# 9_STM32F407_Controller.net
KiCad netlist of a schematic drawn in Altium Designer
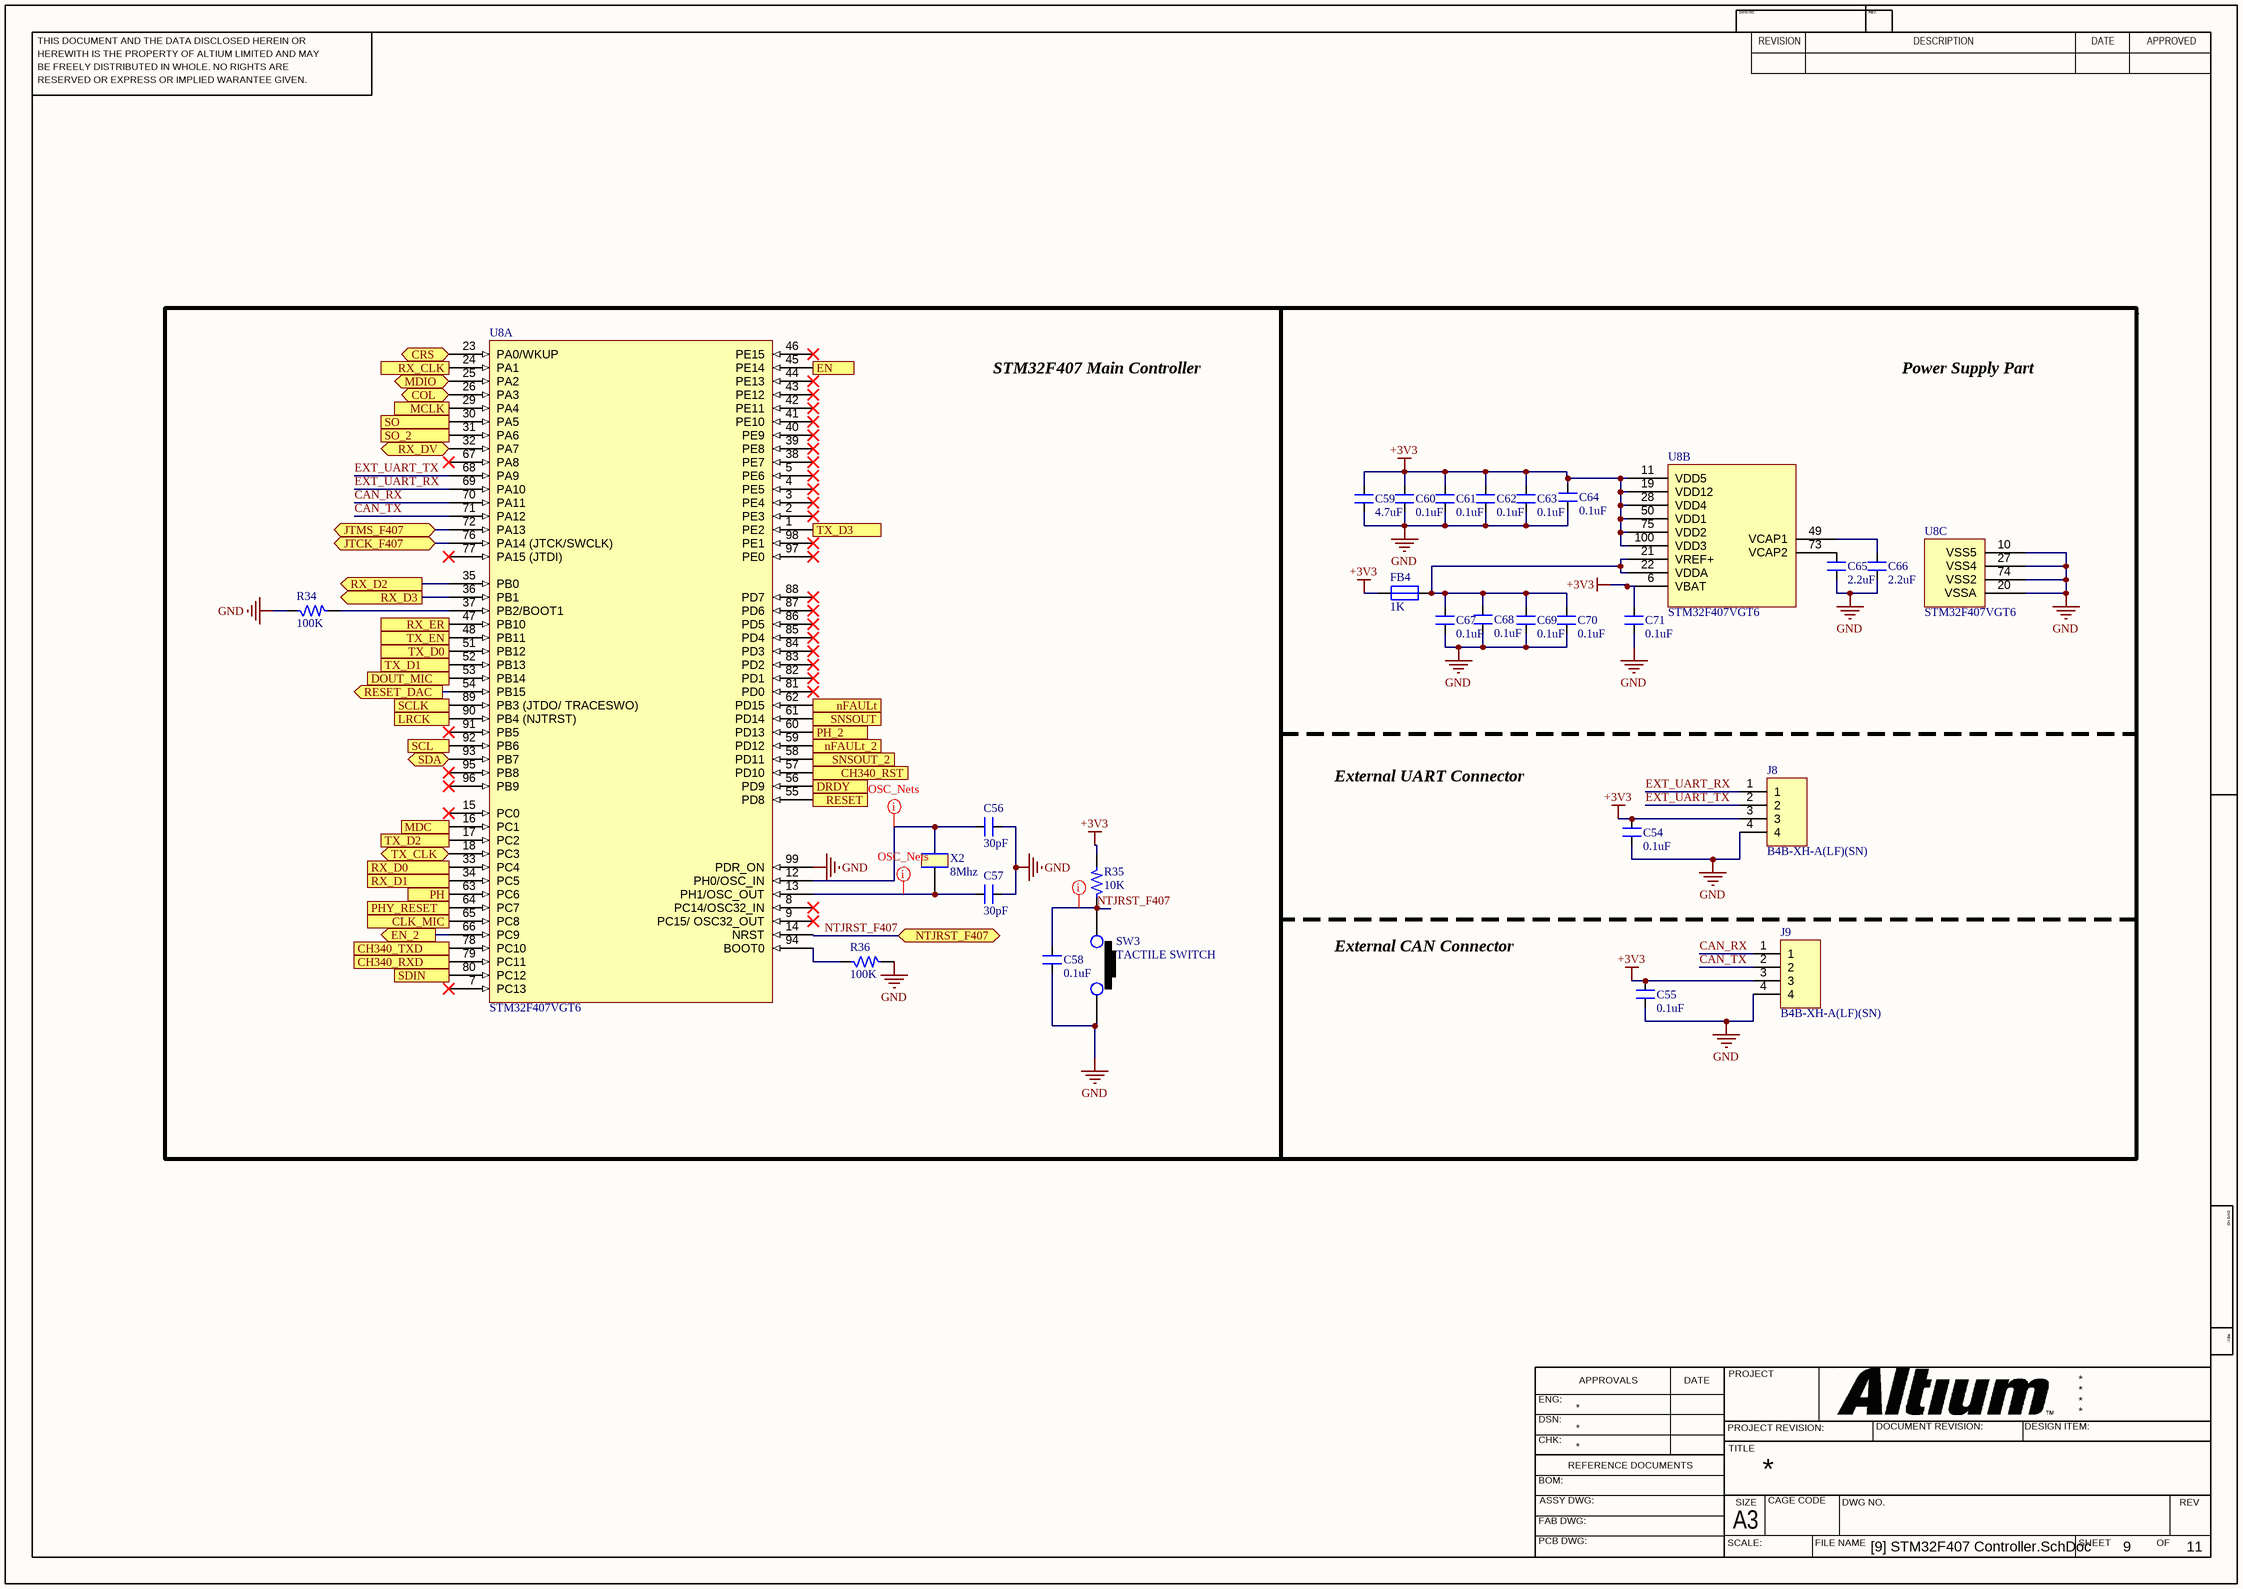
[diagram p0: [9] STM32F407 Controller.SchDoc]

(export (version "E")
  (design (tool "Eeschema 10.0.6"))
  (components
    (comp (ref "C54")
      (value "0.1uF")
      (footprint "CAP_0805")
      (description "0.1µF ±10% 50V Ceramic Capacitor X7R 0805 (2012 Metric)")
      (fields
        (field (name "MANUFACTURER") "Samsung")
        (field (name "MANUFACTURER PART NUMBER") "CL21B104KBCNNNC")
      )
      (libsource (lib "ESTEEMPCBLIB") (part "CAP_0.1uF-50V-10%-0805"))
    )
    (comp (ref "C55")
      (value "0.1uF")
      (footprint "CAP_0805")
      (description "0.1µF ±10% 50V Ceramic Capacitor X7R 0805 (2012 Metric)")
      (fields
        (field (name "MANUFACTURER") "Samsung")
        (field (name "MANUFACTURER PART NUMBER") "CL21B104KBCNNNC")
      )
      (libsource (lib "ESTEEMPCBLIB") (part "CAP_0.1uF-50V-10%-0805"))
    )
    (comp (ref "C56")
      (value "30pF")
      (footprint "CAP_0805")
      (description "±10% 50V Ceramic Capacitor C0G, NP0 0805 (2012 Metric)")
      (fields
        (field (name "MANUFACTURER PART NUMBER") "C0805C300K5GAC7800")
        (field (name "MANUFACTURER") "KEMET")
      )
      (libsource (lib "ESTEEMPCBLIB") (part "CAP_30pF-50V-10%-0805"))
    )
    (comp (ref "C57")
      (value "30pF")
      (footprint "CAP_0805")
      (description "±10% 50V Ceramic Capacitor C0G, NP0 0805 (2012 Metric)")
      (fields
        (field (name "MANUFACTURER PART NUMBER") "C0805C300K5GAC7800")
        (field (name "MANUFACTURER") "KEMET")
      )
      (libsource (lib "ESTEEMPCBLIB") (part "CAP_30pF-50V-10%-0805"))
    )
    (comp (ref "C58")
      (value "0.1uF")
      (footprint "CAP_0805")
      (description "0.1µF ±10% 50V Ceramic Capacitor X7R 0805 (2012 Metric)")
      (fields
        (field (name "MANUFACTURER") "Samsung")
        (field (name "MANUFACTURER PART NUMBER") "CL21B104KBCNNNC")
      )
      (libsource (lib "ESTEEMPCBLIB") (part "CAP_0.1uF-50V-10%-0805"))
    )
    (comp (ref "C59")
      (value "4.7uF")
      (footprint "CAP_0805")
      (description "4.7µF ±10% 50V Ceramic Capacitor X5R 0805 (2012 Metric)")
      (fields
        (field (name "MANUFACTURER") "Yageo")
        (field (name "MANUFACTURER PART NUMBER") "GRM21BR61H475KE51L")
      )
      (libsource (lib "ESTEEMPCBLIB") (part "CAP_4.7uF-50V-10%-0805"))
    )
    (comp (ref "C60")
      (value "0.1uF")
      (footprint "CAP_0805")
      (description "0.1µF ±10% 50V Ceramic Capacitor X7R 0805 (2012 Metric)")
      (fields
        (field (name "MANUFACTURER") "Samsung")
        (field (name "MANUFACTURER PART NUMBER") "CL21B104KBCNNNC")
      )
      (libsource (lib "ESTEEMPCBLIB") (part "CAP_0.1uF-50V-10%-0805"))
    )
    (comp (ref "C61")
      (value "0.1uF")
      (footprint "CAP_0805")
      (description "0.1µF ±10% 50V Ceramic Capacitor X7R 0805 (2012 Metric)")
      (fields
        (field (name "MANUFACTURER") "Samsung")
        (field (name "MANUFACTURER PART NUMBER") "CL21B104KBCNNNC")
      )
      (libsource (lib "ESTEEMPCBLIB") (part "CAP_0.1uF-50V-10%-0805"))
    )
    (comp (ref "C62")
      (value "0.1uF")
      (footprint "CAP_0805")
      (description "0.1µF ±10% 50V Ceramic Capacitor X7R 0805 (2012 Metric)")
      (fields
        (field (name "MANUFACTURER") "Samsung")
        (field (name "MANUFACTURER PART NUMBER") "CL21B104KBCNNNC")
      )
      (libsource (lib "ESTEEMPCBLIB") (part "CAP_0.1uF-50V-10%-0805"))
    )
    (comp (ref "C63")
      (value "0.1uF")
      (footprint "CAP_0805")
      (description "0.1µF ±10% 50V Ceramic Capacitor X7R 0805 (2012 Metric)")
      (fields
        (field (name "MANUFACTURER") "Samsung")
        (field (name "MANUFACTURER PART NUMBER") "CL21B104KBCNNNC")
      )
      (libsource (lib "ESTEEMPCBLIB") (part "CAP_0.1uF-50V-10%-0805"))
    )
    (comp (ref "C64")
      (value "0.1uF")
      (footprint "CAP_0805")
      (description "0.1µF ±10% 50V Ceramic Capacitor X7R 0805 (2012 Metric)")
      (fields
        (field (name "MANUFACTURER") "Samsung")
        (field (name "MANUFACTURER PART NUMBER") "CL21B104KBCNNNC")
      )
      (libsource (lib "ESTEEMPCBLIB") (part "CAP_0.1uF-50V-10%-0805"))
    )
    (comp (ref "C65")
      (value "2.2uF")
      (footprint "CAP_0805")
      (description "2.2µF ±10% 25V Ceramic Capacitor X7R 0805 (2012 Metric)")
      (fields
        (field (name "MANUFACTURER") "KEMET")
        (field (name "MANUFACTURER PART NUMBER") "CL21B225KAFNFNE")
      )
      (libsource (lib "ESTEEMPCBLIB") (part "CAP_2.2uF-25V-10%-0805"))
    )
    (comp (ref "C66")
      (value "2.2uF")
      (footprint "CAP_0805")
      (description "2.2µF ±10% 25V Ceramic Capacitor X7R 0805 (2012 Metric)")
      (fields
        (field (name "MANUFACTURER") "KEMET")
        (field (name "MANUFACTURER PART NUMBER") "CL21B225KAFNFNE")
      )
      (libsource (lib "ESTEEMPCBLIB") (part "CAP_2.2uF-25V-10%-0805"))
    )
    (comp (ref "C67")
      (value "0.1uF")
      (footprint "CAP_0805")
      (description "0.1µF ±10% 50V Ceramic Capacitor X7R 0805 (2012 Metric)")
      (fields
        (field (name "MANUFACTURER") "Samsung")
        (field (name "MANUFACTURER PART NUMBER") "CL21B104KBCNNNC")
      )
      (libsource (lib "ESTEEMPCBLIB") (part "CAP_0.1uF-50V-10%-0805"))
    )
    (comp (ref "C68")
      (value "0.1uF")
      (footprint "CAP_0805")
      (description "0.1µF ±10% 50V Ceramic Capacitor X7R 0805 (2012 Metric)")
      (fields
        (field (name "MANUFACTURER") "Samsung")
        (field (name "MANUFACTURER PART NUMBER") "CL21B104KBCNNNC")
      )
      (libsource (lib "ESTEEMPCBLIB") (part "CAP_0.1uF-50V-10%-0805"))
    )
    (comp (ref "C69")
      (value "0.1uF")
      (footprint "CAP_0805")
      (description "0.1µF ±10% 50V Ceramic Capacitor X7R 0805 (2012 Metric)")
      (fields
        (field (name "MANUFACTURER") "Samsung")
        (field (name "MANUFACTURER PART NUMBER") "CL21B104KBCNNNC")
      )
      (libsource (lib "ESTEEMPCBLIB") (part "CAP_0.1uF-50V-10%-0805"))
    )
    (comp (ref "C70")
      (value "0.1uF")
      (footprint "CAP_0805")
      (description "0.1µF ±10% 50V Ceramic Capacitor X7R 0805 (2012 Metric)")
      (fields
        (field (name "MANUFACTURER") "Samsung")
        (field (name "MANUFACTURER PART NUMBER") "CL21B104KBCNNNC")
      )
      (libsource (lib "ESTEEMPCBLIB") (part "CAP_0.1uF-50V-10%-0805"))
    )
    (comp (ref "C71")
      (value "0.1uF")
      (footprint "CAP_0805")
      (description "0.1µF ±10% 50V Ceramic Capacitor X7R 0805 (2012 Metric)")
      (fields
        (field (name "MANUFACTURER") "Samsung")
        (field (name "MANUFACTURER PART NUMBER") "CL21B104KBCNNNC")
      )
      (libsource (lib "ESTEEMPCBLIB") (part "CAP_0.1uF-50V-10%-0805"))
    )
    (comp (ref "FB4")
      (value "1K")
      (footprint "IND_0805")
      (description "1 kOhms @ 100MHz 1 Power Line Ferrite Bead 0805 (2012 Metric) 1.6A")
      (fields
        (field (name "MANUFACTURER") "Laird")
        (field (name "MANUFACTURER PART NUMBER") "BLM21SP102SH1D")
      )
      (libsource (lib "ESTEEMPCBLIB") (part "FB_1K-100MHZ-1.6A-0805"))
    )
    (comp (ref "J8")
      (value "B4B-XH-A(LF)(SN)")
      (footprint "CON4_100_B4B-XH-A_TH_ST")
      (description "4 Pins, 1 Row 2.54mm Pitch, straight Connector, male")
      (fields (field (name "MANUFACTURER") "Wurth Electronics") (field (name "MATING PART NUMBER") "XHP-4"))
      (libsource (lib "ESTEEMPCBLIB") (part "CON-PLG_4X1-100-ST-TH"))
    )
    (comp (ref "J9")
      (value "B4B-XH-A(LF)(SN)")
      (footprint "CON4_100_B4B-XH-A_TH_ST")
      (description "4 Pins, 1 Row 2.54mm Pitch, straight Connector, male")
      (fields (field (name "MANUFACTURER") "Wurth Electronics") (field (name "MATING PART NUMBER") "XHP-4"))
      (libsource (lib "ESTEEMPCBLIB") (part "CON-PLG_4X1-100-ST-TH"))
    )
    (comp (ref "R34")
      (value "100K")
      (footprint "RES_0603")
      (description "100 kOhms ±1% 0.1W, 1/10W Chip Resistor 0603 (1608 Metric) Automotive AEC-Q200 Thick Film")
      (fields
        (field (name "MANUFACTURER") "Stackpole Electronics")
        (field (name "MANUFACTURER PART NUMBER") "RMCF0603FT100K")
      )
      (libsource (lib "ESTEEMPCBLIB") (part "RES_100K-0.1W-1%-0603"))
    )
    (comp (ref "R35")
      (value "10K")
      (footprint "RES_0603")
      (description "10 kOhms ±1% 0.1W, 1/10W Chip Resistor 0603 (1608 Metric) Automotive AEC-Q200 Thick Film")
      (fields (field (name "MANUFACTURER") "Walsin") (field (name "MANUFACTURER PART NUMBER") "WR06X1002FTL"))
      (libsource (lib "ESTEEMPCBLIB") (part "RES_10K-0.1W-1%-0603"))
    )
    (comp (ref "R36")
      (value "100K")
      (footprint "RES_0603")
      (description "100 kOhms ±1% 0.1W, 1/10W Chip Resistor 0603 (1608 Metric) Automotive AEC-Q200 Thick Film")
      (fields
        (field (name "MANUFACTURER") "Stackpole Electronics")
        (field (name "MANUFACTURER PART NUMBER") "RMCF0603FT100K")
      )
      (libsource (lib "ESTEEMPCBLIB") (part "RES_100K-0.1W-1%-0603"))
    )
    (comp (ref "SW3")
      (value "TACTILE SWITCH")
      (footprint "SW_342_SMD")
      (description "Tactile Switch SPST-NO Top Actuated Surface Mount")
      (fields
        (field (name "MANUFACTURER") "ITT C&K")
        (field (name "MANUFACTURER PART NUMBER") "RS-282G05A3-SMRT")
      )
      (libsource (lib "ESTEEMPCBLIB") (part "SW1_RS-282G05A3-SMRT-SMD"))
    )
    (comp (ref "U8")
      (value "STM32F407VGT6")
      (footprint "QFN100_19.6_669_58X10_SMD")
      (description "ARM® Cortex®-M4 STM32F4 Microcontroller IC 32-Bit 168MHz 1MB (1M x 8) FLASH 100-LQFP (14x14)")
      (fields (field (name "MANUFACTURER") "STMicroelectronics"))
      (libsource (lib "ESTEEMPCBLIB") (part "IC_STM32F407VGT6"))
    )
    (comp (ref "X2")
      (value "8Mhz")
      (footprint "XTAL_314_240X47_SMD")
      (description "8MHz ±30ppm Crystal 32pF 60 Ohms HC-49/US")
      (fields
        (field (name "MANUFACTURER") "Fox Electronics")
        (field (name "MANUFACTURER PART NUMBER") "ECS-80-32-5PX-TR")
      )
      (libsource (lib "ESTEEMPCBLIB") (part "XTAL_8MHZ-ECS-80-32-5PX-SMD"))
    )
  )
  (nets
    (net (code "1") (name "+3V3") (class "Default")
      (node (ref "C54") (pin "2") (pinfunction "2_2") (pintype "passive"))
      (node (ref "C55") (pin "2") (pinfunction "2_2") (pintype "passive"))
      (node (ref "C59") (pin "2") (pinfunction "2_2") (pintype "passive"))
      (node (ref "C60") (pin "2") (pinfunction "2_2") (pintype "passive"))
      (node (ref "C61") (pin "2") (pinfunction "2_2") (pintype "passive"))
      (node (ref "C62") (pin "2") (pinfunction "2_2") (pintype "passive"))
      (node (ref "C63") (pin "2") (pinfunction "2_2") (pintype "passive"))
      (node (ref "C64") (pin "2") (pinfunction "2_2") (pintype "passive"))
      (node (ref "C71") (pin "2") (pinfunction "2_2") (pintype "passive"))
      (node (ref "FB4") (pin "1") (pinfunction "1_1") (pintype "passive"))
      (node (ref "J8") (pin "3") (pinfunction "3_3") (pintype "passive"))
      (node (ref "J9") (pin "3") (pinfunction "3_3") (pintype "passive"))
      (node (ref "R35") (pin "2") (pinfunction "2_2") (pintype "passive"))
      (node (ref "U8") (pin "100") (pinfunction "VDD3_100") (pintype "passive"))
      (node (ref "U8") (pin "11") (pinfunction "VDD5_11") (pintype "passive"))
      (node (ref "U8") (pin "19") (pinfunction "VDD12_19") (pintype "passive"))
      (node (ref "U8") (pin "28") (pinfunction "VDD4_28") (pintype "passive"))
      (node (ref "U8") (pin "50") (pinfunction "VDD1_50") (pintype "passive"))
      (node (ref "U8") (pin "6") (pinfunction "VBAT_6") (pintype "passive"))
      (node (ref "U8") (pin "75") (pinfunction "VDD2_75") (pintype "passive"))
    )
    (net (code "2") (name "/CAN_RX") (class "Default")
      (node (ref "J9") (pin "1") (pinfunction "1_1") (pintype "passive"))
      (node (ref "U8") (pin "70") (pinfunction "PA11_70") (pintype "input"))
    )
    (net (code "3") (name "/CAN_TX") (class "Default")
      (node (ref "J9") (pin "2") (pinfunction "2_2") (pintype "passive"))
      (node (ref "U8") (pin "71") (pinfunction "PA12_71") (pintype "input"))
    )
    (net (code "4") (name "/CH340_RST") (class "Default")
      (node (ref "U8") (pin "57") (pinfunction "PD10_57") (pintype "input"))
    )
    (net (code "5") (name "/CH340_RXD") (class "Default")
      (node (ref "U8") (pin "79") (pinfunction "PC11_79") (pintype "input"))
    )
    (net (code "6") (name "/CH340_TXD") (class "Default")
      (node (ref "U8") (pin "78") (pinfunction "PC10_78") (pintype "input"))
    )
    (net (code "7") (name "/CLK_MIC") (class "Default")
      (node (ref "U8") (pin "65") (pinfunction "PC8_65") (pintype "input"))
    )
    (net (code "8") (name "/COL") (class "Default")
      (node (ref "U8") (pin "26") (pinfunction "PA3_26") (pintype "input"))
    )
    (net (code "9") (name "/CRS") (class "Default")
      (node (ref "U8") (pin "23") (pinfunction "PA0/WKUP_23") (pintype "input"))
    )
    (net (code "10") (name "/DOUT_MIC") (class "Default")
      (node (ref "U8") (pin "53") (pinfunction "PB14_53") (pintype "input"))
    )
    (net (code "11") (name "/DRDY") (class "Default")
      (node (ref "U8") (pin "56") (pinfunction "PD9_56") (pintype "input"))
    )
    (net (code "12") (name "/EN") (class "Default")
      (node (ref "U8") (pin "45") (pinfunction "PE14_45") (pintype "input"))
    )
    (net (code "13") (name "/EN_2") (class "Default")
      (node (ref "U8") (pin "66") (pinfunction "PC9_66") (pintype "input"))
    )
    (net (code "14") (name "/EXT_UART_RX") (class "Default")
      (node (ref "J8") (pin "1") (pinfunction "1_1") (pintype "passive"))
      (node (ref "U8") (pin "69") (pinfunction "PA10_69") (pintype "input"))
    )
    (net (code "15") (name "/EXT_UART_TX") (class "Default")
      (node (ref "J8") (pin "2") (pinfunction "2_2") (pintype "passive"))
      (node (ref "U8") (pin "68") (pinfunction "PA9_68") (pintype "input"))
    )
    (net (code "16") (name "/JTCK_F407") (class "Default")
      (node (ref "U8") (pin "76") (pinfunction "PA14_(JTCK/SWCLK)_76") (pintype "input"))
    )
    (net (code "17") (name "/JTMS_F407") (class "Default")
      (node (ref "U8") (pin "72") (pinfunction "PA13_72") (pintype "input"))
    )
    (net (code "18") (name "/LRCK") (class "Default")
      (node (ref "U8") (pin "90") (pinfunction "PB4_(NJTRST)_90") (pintype "input"))
    )
    (net (code "19") (name "/MCLK") (class "Default")
      (node (ref "U8") (pin "29") (pinfunction "PA4_29") (pintype "input"))
    )
    (net (code "20") (name "/MDC") (class "Default")
      (node (ref "U8") (pin "16") (pinfunction "PC1_16") (pintype "input"))
    )
    (net (code "21") (name "/MDIO") (class "Default")
      (node (ref "U8") (pin "25") (pinfunction "PA2_25") (pintype "input"))
    )
    (net (code "22") (name "/NTJRST_F407") (class "Default")
      (node (ref "C58") (pin "2") (pinfunction "2_2") (pintype "passive"))
      (node (ref "R35") (pin "1") (pinfunction "1_1") (pintype "passive"))
      (node (ref "SW3") (pin "1") (pinfunction "1_1") (pintype "passive"))
      (node (ref "U8") (pin "14") (pinfunction "NRST_14") (pintype "input"))
    )
    (net (code "23") (name "/PH") (class "Default")
      (node (ref "U8") (pin "63") (pinfunction "PC6_63") (pintype "input"))
    )
    (net (code "24") (name "/PHY_RESET") (class "Default")
      (node (ref "U8") (pin "64") (pinfunction "PC7_64") (pintype "input"))
    )
    (net (code "25") (name "/PH_2") (class "Default")
      (node (ref "U8") (pin "60") (pinfunction "PD13_60") (pintype "input"))
    )
    (net (code "26") (name "/RESET") (class "Default")
      (node (ref "U8") (pin "55") (pinfunction "PD8_55") (pintype "input"))
    )
    (net (code "27") (name "/RESET_DAC") (class "Default")
      (node (ref "U8") (pin "54") (pinfunction "PB15_54") (pintype "input"))
    )
    (net (code "28") (name "/RX_CLK") (class "Default")
      (node (ref "U8") (pin "24") (pinfunction "PA1_24") (pintype "input"))
    )
    (net (code "29") (name "/RX_D0") (class "Default")
      (node (ref "U8") (pin "33") (pinfunction "PC4_33") (pintype "input"))
    )
    (net (code "30") (name "/RX_D1") (class "Default")
      (node (ref "U8") (pin "34") (pinfunction "PC5_34") (pintype "input"))
    )
    (net (code "31") (name "/RX_D2") (class "Default")
      (node (ref "U8") (pin "35") (pinfunction "PB0_35") (pintype "input"))
    )
    (net (code "32") (name "/RX_D3") (class "Default")
      (node (ref "U8") (pin "36") (pinfunction "PB1_36") (pintype "input"))
    )
    (net (code "33") (name "/RX_DV") (class "Default")
      (node (ref "U8") (pin "32") (pinfunction "PA7_32") (pintype "input"))
    )
    (net (code "34") (name "/RX_ER") (class "Default")
      (node (ref "U8") (pin "47") (pinfunction "PB10_47") (pintype "input"))
    )
    (net (code "35") (name "/SCL") (class "Default")
      (node (ref "U8") (pin "92") (pinfunction "PB6_92") (pintype "input"))
    )
    (net (code "36") (name "/SCLK") (class "Default")
      (node (ref "U8") (pin "89") (pinfunction "PB3_(JTDO/_TRACESWO)_89") (pintype "input"))
    )
    (net (code "37") (name "/SDA") (class "Default")
      (node (ref "U8") (pin "93") (pinfunction "PB7_93") (pintype "input"))
    )
    (net (code "38") (name "/SDIN") (class "Default")
      (node (ref "U8") (pin "80") (pinfunction "PC12_80") (pintype "input"))
    )
    (net (code "39") (name "/SNSOUT") (class "Default")
      (node (ref "U8") (pin "61") (pinfunction "PD14_61") (pintype "input"))
    )
    (net (code "40") (name "/SNSOUT_2") (class "Default")
      (node (ref "U8") (pin "58") (pinfunction "PD11_58") (pintype "input"))
    )
    (net (code "41") (name "/SO") (class "Default")
      (node (ref "U8") (pin "30") (pinfunction "PA5_30") (pintype "input"))
    )
    (net (code "42") (name "/SO_2") (class "Default")
      (node (ref "U8") (pin "31") (pinfunction "PA6_31") (pintype "input"))
    )
    (net (code "43") (name "/TX_CLK") (class "Default")
      (node (ref "U8") (pin "18") (pinfunction "PC3_18") (pintype "input"))
    )
    (net (code "44") (name "/TX_D0") (class "Default")
      (node (ref "U8") (pin "51") (pinfunction "PB12_51") (pintype "input"))
    )
    (net (code "45") (name "/TX_D1") (class "Default")
      (node (ref "U8") (pin "52") (pinfunction "PB13_52") (pintype "input"))
    )
    (net (code "46") (name "/TX_D2") (class "Default")
      (node (ref "U8") (pin "17") (pinfunction "PC2_17") (pintype "input"))
    )
    (net (code "47") (name "/TX_D3") (class "Default")
      (node (ref "U8") (pin "1") (pinfunction "PE2_1") (pintype "input"))
    )
    (net (code "48") (name "/TX_EN") (class "Default")
      (node (ref "U8") (pin "48") (pinfunction "PB11_48") (pintype "input"))
    )
    (net (code "49") (name "/nFAULt") (class "Default")
      (node (ref "U8") (pin "62") (pinfunction "PD15_62") (pintype "input"))
    )
    (net (code "50") (name "/nFAULt_2") (class "Default")
      (node (ref "U8") (pin "59") (pinfunction "PD12_59") (pintype "input"))
    )
    (net (code "51") (name "GND") (class "Default")
      (node (ref "C54") (pin "1") (pinfunction "1_1") (pintype "passive"))
      (node (ref "C55") (pin "1") (pinfunction "1_1") (pintype "passive"))
      (node (ref "C56") (pin "1") (pinfunction "1_1") (pintype "passive"))
      (node (ref "C57") (pin "1") (pinfunction "1_1") (pintype "passive"))
      (node (ref "C58") (pin "1") (pinfunction "1_1") (pintype "passive"))
      (node (ref "C59") (pin "1") (pinfunction "1_1") (pintype "passive"))
      (node (ref "C60") (pin "1") (pinfunction "1_1") (pintype "passive"))
      (node (ref "C61") (pin "1") (pinfunction "1_1") (pintype "passive"))
      (node (ref "C62") (pin "1") (pinfunction "1_1") (pintype "passive"))
      (node (ref "C63") (pin "1") (pinfunction "1_1") (pintype "passive"))
      (node (ref "C64") (pin "1") (pinfunction "1_1") (pintype "passive"))
      (node (ref "C65") (pin "1") (pinfunction "1_1") (pintype "passive"))
      (node (ref "C66") (pin "1") (pinfunction "1_1") (pintype "passive"))
      (node (ref "C67") (pin "1") (pinfunction "1_1") (pintype "passive"))
      (node (ref "C68") (pin "1") (pinfunction "1_1") (pintype "passive"))
      (node (ref "C69") (pin "1") (pinfunction "1_1") (pintype "passive"))
      (node (ref "C70") (pin "1") (pinfunction "1_1") (pintype "passive"))
      (node (ref "C71") (pin "1") (pinfunction "1_1") (pintype "passive"))
      (node (ref "J8") (pin "4") (pinfunction "4_4") (pintype "passive"))
      (node (ref "J9") (pin "4") (pinfunction "4_4") (pintype "passive"))
      (node (ref "R34") (pin "1") (pinfunction "1_1") (pintype "passive"))
      (node (ref "R36") (pin "2") (pinfunction "2_2") (pintype "passive"))
      (node (ref "SW3") (pin "2") (pinfunction "2_2") (pintype "passive"))
      (node (ref "U8") (pin "10") (pinfunction "VSS5_10") (pintype "passive"))
      (node (ref "U8") (pin "20") (pinfunction "VSSA_20") (pintype "passive"))
      (node (ref "U8") (pin "27") (pinfunction "VSS4_27") (pintype "passive"))
      (node (ref "U8") (pin "74") (pinfunction "VSS2_74") (pintype "passive"))
      (node (ref "U8") (pin "99") (pinfunction "PDR_ON_99") (pintype "input"))
    )
    (net (code "52") (name "Net-(U8A-BOOT0)") (class "Default")
      (node (ref "R36") (pin "1") (pinfunction "1_1") (pintype "passive"))
      (node (ref "U8") (pin "94") (pinfunction "BOOT0_94") (pintype "input"))
    )
    (net (code "53") (name "Net-(U8A-PB2{slash}BOOT1)") (class "Default")
      (node (ref "R34") (pin "2") (pinfunction "2_2") (pintype "passive"))
      (node (ref "U8") (pin "37") (pinfunction "PB2/BOOT1_37") (pintype "input"))
    )
    (net (code "54") (name "Net-(U8A-PH0{slash}OSC_IN)") (class "Default")
      (node (ref "C56") (pin "2") (pinfunction "2_2") (pintype "passive"))
      (node (ref "U8") (pin "12") (pinfunction "PH0/OSC_IN_12") (pintype "input"))
      (node (ref "X2") (pin "2") (pinfunction "2_2") (pintype "passive"))
    )
    (net (code "55") (name "Net-(U8A-PH1{slash}OSC_OUT)") (class "Default")
      (node (ref "C57") (pin "2") (pinfunction "2_2") (pintype "passive"))
      (node (ref "U8") (pin "13") (pinfunction "PH1/OSC_OUT_13") (pintype "input"))
      (node (ref "X2") (pin "1") (pinfunction "1_1") (pintype "passive"))
    )
    (net (code "56") (name "Net-(U8B-VCAP1)") (class "Default")
      (node (ref "C66") (pin "2") (pinfunction "2_2") (pintype "passive"))
      (node (ref "U8") (pin "49") (pinfunction "VCAP1_49") (pintype "passive"))
    )
    (net (code "57") (name "Net-(U8B-VCAP2)") (class "Default")
      (node (ref "C65") (pin "2") (pinfunction "2_2") (pintype "passive"))
      (node (ref "U8") (pin "73") (pinfunction "VCAP2_73") (pintype "passive"))
    )
    (net (code "58") (name "Net-(U8B-VDDA)") (class "Default")
      (node (ref "C67") (pin "2") (pinfunction "2_2") (pintype "passive"))
      (node (ref "C68") (pin "2") (pinfunction "2_2") (pintype "passive"))
      (node (ref "C69") (pin "2") (pinfunction "2_2") (pintype "passive"))
      (node (ref "C70") (pin "2") (pinfunction "2_2") (pintype "passive"))
      (node (ref "FB4") (pin "2") (pinfunction "2_2") (pintype "passive"))
      (node (ref "U8") (pin "21") (pinfunction "VREF+_21") (pintype "passive"))
      (node (ref "U8") (pin "22") (pinfunction "VDDA_22") (pintype "passive"))
    )
    (net (code "59") (name "unconnected-(U8A-PA8-Pad67)") (class "Default")
      (node (ref "U8") (pin "67") (pinfunction "PA8_67") (pintype "input+no_connect"))
    )
    (net (code "60") (name "unconnected-(U8A-PA15_(JTDI)-Pad77)") (class "Default")
      (node (ref "U8") (pin "77") (pinfunction "PA15_(JTDI)_77") (pintype "input+no_connect"))
    )
    (net (code "61") (name "unconnected-(U8A-PB5-Pad91)") (class "Default")
      (node (ref "U8") (pin "91") (pinfunction "PB5_91") (pintype "input+no_connect"))
    )
    (net (code "62") (name "unconnected-(U8A-PB8-Pad95)") (class "Default")
      (node (ref "U8") (pin "95") (pinfunction "PB8_95") (pintype "input+no_connect"))
    )
    (net (code "63") (name "unconnected-(U8A-PB9-Pad96)") (class "Default")
      (node (ref "U8") (pin "96") (pinfunction "PB9_96") (pintype "input+no_connect"))
    )
    (net (code "64") (name "unconnected-(U8A-PC0-Pad15)") (class "Default")
      (node (ref "U8") (pin "15") (pinfunction "PC0_15") (pintype "input+no_connect"))
    )
    (net (code "65") (name "unconnected-(U8A-PC13-Pad7)") (class "Default")
      (node (ref "U8") (pin "7") (pinfunction "PC13_7") (pintype "input+no_connect"))
    )
    (net (code "66") (name "unconnected-(U8A-PC14{slash}OSC32_IN-Pad8)") (class "Default")
      (node (ref "U8") (pin "8") (pinfunction "PC14/OSC32_IN_8") (pintype "input+no_connect"))
    )
    (net (code "67") (name "unconnected-(U8A-PC15{slash}_OSC32_OUT-Pad9)") (class "Default")
      (node (ref "U8") (pin "9") (pinfunction "PC15/_OSC32_OUT_9") (pintype "input+no_connect"))
    )
    (net (code "68") (name "unconnected-(U8A-PD0-Pad81)") (class "Default")
      (node (ref "U8") (pin "81") (pinfunction "PD0_81") (pintype "input+no_connect"))
    )
    (net (code "69") (name "unconnected-(U8A-PD1-Pad82)") (class "Default")
      (node (ref "U8") (pin "82") (pinfunction "PD1_82") (pintype "input+no_connect"))
    )
    (net (code "70") (name "unconnected-(U8A-PD2-Pad83)") (class "Default")
      (node (ref "U8") (pin "83") (pinfunction "PD2_83") (pintype "input+no_connect"))
    )
    (net (code "71") (name "unconnected-(U8A-PD3-Pad84)") (class "Default")
      (node (ref "U8") (pin "84") (pinfunction "PD3_84") (pintype "input+no_connect"))
    )
    (net (code "72") (name "unconnected-(U8A-PD4-Pad85)") (class "Default")
      (node (ref "U8") (pin "85") (pinfunction "PD4_85") (pintype "input+no_connect"))
    )
    (net (code "73") (name "unconnected-(U8A-PD5-Pad86)") (class "Default")
      (node (ref "U8") (pin "86") (pinfunction "PD5_86") (pintype "input+no_connect"))
    )
    (net (code "74") (name "unconnected-(U8A-PD6-Pad87)") (class "Default")
      (node (ref "U8") (pin "87") (pinfunction "PD6_87") (pintype "input+no_connect"))
    )
    (net (code "75") (name "unconnected-(U8A-PD7-Pad88)") (class "Default")
      (node (ref "U8") (pin "88") (pinfunction "PD7_88") (pintype "input+no_connect"))
    )
    (net (code "76") (name "unconnected-(U8A-PE0-Pad97)") (class "Default")
      (node (ref "U8") (pin "97") (pinfunction "PE0_97") (pintype "input+no_connect"))
    )
    (net (code "77") (name "unconnected-(U8A-PE1-Pad98)") (class "Default")
      (node (ref "U8") (pin "98") (pinfunction "PE1_98") (pintype "input+no_connect"))
    )
    (net (code "78") (name "unconnected-(U8A-PE3-Pad2)") (class "Default")
      (node (ref "U8") (pin "2") (pinfunction "PE3_2") (pintype "input+no_connect"))
    )
    (net (code "79") (name "unconnected-(U8A-PE4-Pad3)") (class "Default")
      (node (ref "U8") (pin "3") (pinfunction "PE4_3") (pintype "input+no_connect"))
    )
    (net (code "80") (name "unconnected-(U8A-PE5-Pad4)") (class "Default")
      (node (ref "U8") (pin "4") (pinfunction "PE5_4") (pintype "input+no_connect"))
    )
    (net (code "81") (name "unconnected-(U8A-PE6-Pad5)") (class "Default")
      (node (ref "U8") (pin "5") (pinfunction "PE6_5") (pintype "input+no_connect"))
    )
    (net (code "82") (name "unconnected-(U8A-PE7-Pad38)") (class "Default")
      (node (ref "U8") (pin "38") (pinfunction "PE7_38") (pintype "input+no_connect"))
    )
    (net (code "83") (name "unconnected-(U8A-PE8-Pad39)") (class "Default")
      (node (ref "U8") (pin "39") (pinfunction "PE8_39") (pintype "input+no_connect"))
    )
    (net (code "84") (name "unconnected-(U8A-PE9-Pad40)") (class "Default")
      (node (ref "U8") (pin "40") (pinfunction "PE9_40") (pintype "input+no_connect"))
    )
    (net (code "85") (name "unconnected-(U8A-PE10-Pad41)") (class "Default")
      (node (ref "U8") (pin "41") (pinfunction "PE10_41") (pintype "input+no_connect"))
    )
    (net (code "86") (name "unconnected-(U8A-PE11-Pad42)") (class "Default")
      (node (ref "U8") (pin "42") (pinfunction "PE11_42") (pintype "input+no_connect"))
    )
    (net (code "87") (name "unconnected-(U8A-PE12-Pad43)") (class "Default")
      (node (ref "U8") (pin "43") (pinfunction "PE12_43") (pintype "input+no_connect"))
    )
    (net (code "88") (name "unconnected-(U8A-PE13-Pad44)") (class "Default")
      (node (ref "U8") (pin "44") (pinfunction "PE13_44") (pintype "input+no_connect"))
    )
    (net (code "89") (name "unconnected-(U8A-PE15-Pad46)") (class "Default")
      (node (ref "U8") (pin "46") (pinfunction "PE15_46") (pintype "input+no_connect"))
    )
  )
)
